# lcdi2c.net
KiCad netlist of a schematic drawn in Altium Designer
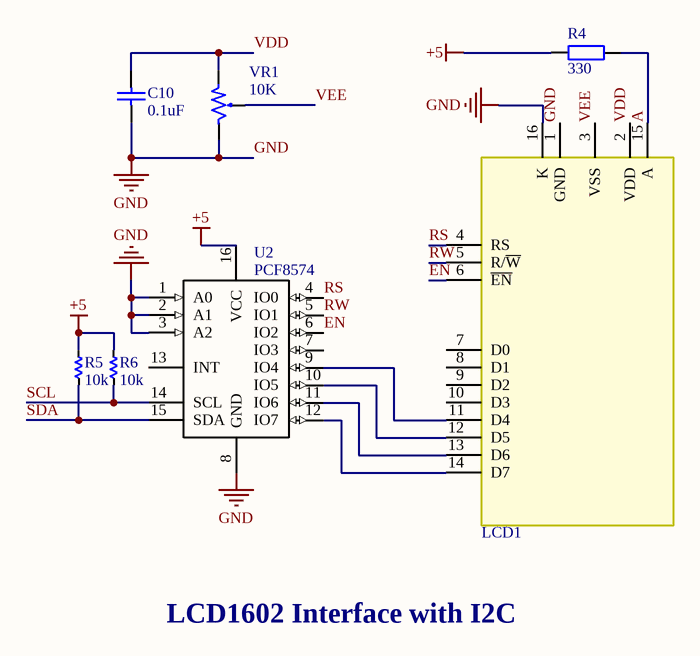
[diagram p0: lcdi2c.SchDoc]

(export (version "E")
  (design (tool "Eeschema 10.0.6"))
  (components
    (comp (ref "C10")
      (value "0.1uF")
      (footprint "CNP")
      (description "Capacitor (Semiconductor SIM Model)")
      (fields (field (name "PUBLISHER") "Altium Limited"))
      (libsource (lib "syhaunguyen") (part "Cap Semi"))
    )
    (comp (ref "LCD1")
      (value "LCD16x2A")
      (footprint "LCD16X2")
      (description "LCD dipslay 16 char, 2 line")
      (libsource (lib "syhaunguyen") (part "LCD16x2"))
    )
    (comp (ref "R4")
      (value "330")
      (footprint "R1/4W")
      (description "Resistor 1/4W")
      (libsource (lib "syhaunguyen") (part "R1/4W"))
    )
    (comp (ref "R5")
      (value "10k")
      (footprint "RES-SMD-0805")
      (description "Resistor")
      (fields
        (field (name "MANUFACTURER") "Generic Components")
        (field (name "PUBLISHER") "Altium Hobart Technology Centre")
      )
      (libsource (lib "LIBRARY1") (part "Res-SMD"))
    )
    (comp (ref "R6")
      (value "10k")
      (footprint "RES-SMD-0805")
      (description "Resistor")
      (fields
        (field (name "MANUFACTURER") "Generic Components")
        (field (name "PUBLISHER") "Altium Hobart Technology Centre")
      )
      (libsource (lib "LIBRARY1") (part "Res-SMD"))
    )
    (comp (ref "U2")
      (value "PCF8574")
      (footprint "SO16L")
      (description "I2C PORT EXPANDER")
      (fields
        (field (name "MANUFACTURER PART NUMBER") "PCF8574T/3,512")
        (field (name "MANUFACTURER") "NXP Semiconductors")
      )
      (libsource (lib "Thư Viện Altium FULL HD") (part "PCF8574"))
    )
    (comp (ref "VR1")
      (value "10K")
      (footprint "VR")
      (description "Var Resistor")
      (libsource (lib "syhaunguyen") (part "VR1"))
    )
  )
  (nets
    (net (code "1") (name "+5") (class "Default")
      (node (ref "R4") (pin "1") (pinfunction "1_1") (pintype "passive"))
      (node (ref "R5") (pin "1") (pinfunction "1_1") (pintype "passive"))
      (node (ref "R6") (pin "1") (pinfunction "1_1") (pintype "passive"))
      (node (ref "U2") (pin "16") (pinfunction "VCC_16") (pintype "passive"))
    )
    (net (code "2") (name "/A") (class "Default")
      (node (ref "LCD1") (pin "15") (pinfunction "A_15") (pintype "passive"))
      (node (ref "R4") (pin "2") (pinfunction "2_2") (pintype "passive"))
    )
    (net (code "3") (name "/EN") (class "Default")
      (node (ref "LCD1") (pin "6") (pinfunction "~{EN}_6") (pintype "passive"))
      (node (ref "U2") (pin "6") (pinfunction "IO2_6") (pintype "bidirectional"))
    )
    (net (code "4") (name "/RS") (class "Default")
      (node (ref "LCD1") (pin "4") (pinfunction "RS_4") (pintype "passive"))
      (node (ref "U2") (pin "4") (pinfunction "IO0_4") (pintype "bidirectional"))
    )
    (net (code "5") (name "/RW") (class "Default")
      (node (ref "LCD1") (pin "5") (pinfunction "R/~{W}_5") (pintype "passive"))
      (node (ref "U2") (pin "5") (pinfunction "IO1_5") (pintype "bidirectional"))
    )
    (net (code "6") (name "/SCL") (class "Default")
      (node (ref "R6") (pin "2") (pinfunction "2_2") (pintype "passive"))
      (node (ref "U2") (pin "14") (pinfunction "SCL_14") (pintype "open_collector"))
    )
    (net (code "7") (name "/SDA") (class "Default")
      (node (ref "R5") (pin "2") (pinfunction "2_2") (pintype "passive"))
      (node (ref "U2") (pin "15") (pinfunction "SDA_15") (pintype "open_collector"))
    )
    (net (code "8") (name "/VDD") (class "Default")
      (node (ref "C10") (pin "2") (pinfunction "2_2") (pintype "passive"))
      (node (ref "LCD1") (pin "2") (pinfunction "VDD_2") (pintype "passive"))
      (node (ref "VR1") (pin "1") (pinfunction "1_1") (pintype "passive"))
    )
    (net (code "9") (name "/VEE") (class "Default")
      (node (ref "LCD1") (pin "3") (pinfunction "VSS_3") (pintype "passive"))
      (node (ref "VR1") (pin "2") (pinfunction "2_2") (pintype "passive"))
    )
    (net (code "10") (name "GND") (class "Default")
      (node (ref "C10") (pin "1") (pinfunction "1_1") (pintype "passive"))
      (node (ref "LCD1") (pin "1") (pinfunction "GND_1") (pintype "passive"))
      (node (ref "LCD1") (pin "16") (pinfunction "K_16") (pintype "passive"))
      (node (ref "U2") (pin "1") (pinfunction "A0_1") (pintype "input"))
      (node (ref "U2") (pin "2") (pinfunction "A1_2") (pintype "input"))
      (node (ref "U2") (pin "3") (pinfunction "A2_3") (pintype "input"))
      (node (ref "U2") (pin "8") (pinfunction "GND_8") (pintype "passive"))
      (node (ref "VR1") (pin "3") (pinfunction "3_3") (pintype "passive"))
    )
    (net (code "11") (name "Net-(LCD1-D4)") (class "Default")
      (node (ref "LCD1") (pin "11") (pinfunction "D4_11") (pintype "passive"))
      (node (ref "U2") (pin "9") (pinfunction "IO4_9") (pintype "bidirectional"))
    )
    (net (code "12") (name "Net-(LCD1-D5)") (class "Default")
      (node (ref "LCD1") (pin "12") (pinfunction "D5_12") (pintype "passive"))
      (node (ref "U2") (pin "10") (pinfunction "IO5_10") (pintype "bidirectional"))
    )
    (net (code "13") (name "Net-(LCD1-D6)") (class "Default")
      (node (ref "LCD1") (pin "13") (pinfunction "D6_13") (pintype "passive"))
      (node (ref "U2") (pin "11") (pinfunction "IO6_11") (pintype "bidirectional"))
    )
    (net (code "14") (name "Net-(LCD1-D7)") (class "Default")
      (node (ref "LCD1") (pin "14") (pinfunction "D7_14") (pintype "passive"))
      (node (ref "U2") (pin "12") (pinfunction "IO7_12") (pintype "bidirectional"))
    )
    (net (code "15") (name "unconnected-(LCD1-D0-Pad7)") (class "Default")
      (node (ref "LCD1") (pin "7") (pinfunction "D0_7") (pintype "passive"))
    )
    (net (code "16") (name "unconnected-(LCD1-D1-Pad8)") (class "Default")
      (node (ref "LCD1") (pin "8") (pinfunction "D1_8") (pintype "passive"))
    )
    (net (code "17") (name "unconnected-(LCD1-D2-Pad9)") (class "Default")
      (node (ref "LCD1") (pin "9") (pinfunction "D2_9") (pintype "passive"))
    )
    (net (code "18") (name "unconnected-(LCD1-D3-Pad10)") (class "Default")
      (node (ref "LCD1") (pin "10") (pinfunction "D3_10") (pintype "passive"))
    )
    (net (code "19") (name "unconnected-(U2-INT-Pad13)") (class "Default")
      (node (ref "U2") (pin "13") (pinfunction "INT_13") (pintype "open_collector"))
    )
    (net (code "20") (name "unconnected-(U2-IO3-Pad7)") (class "Default")
      (node (ref "U2") (pin "7") (pinfunction "IO3_7") (pintype "bidirectional"))
    )
  )
)
